# Top.net
KiCad netlist of a schematic drawn in Altium Designer
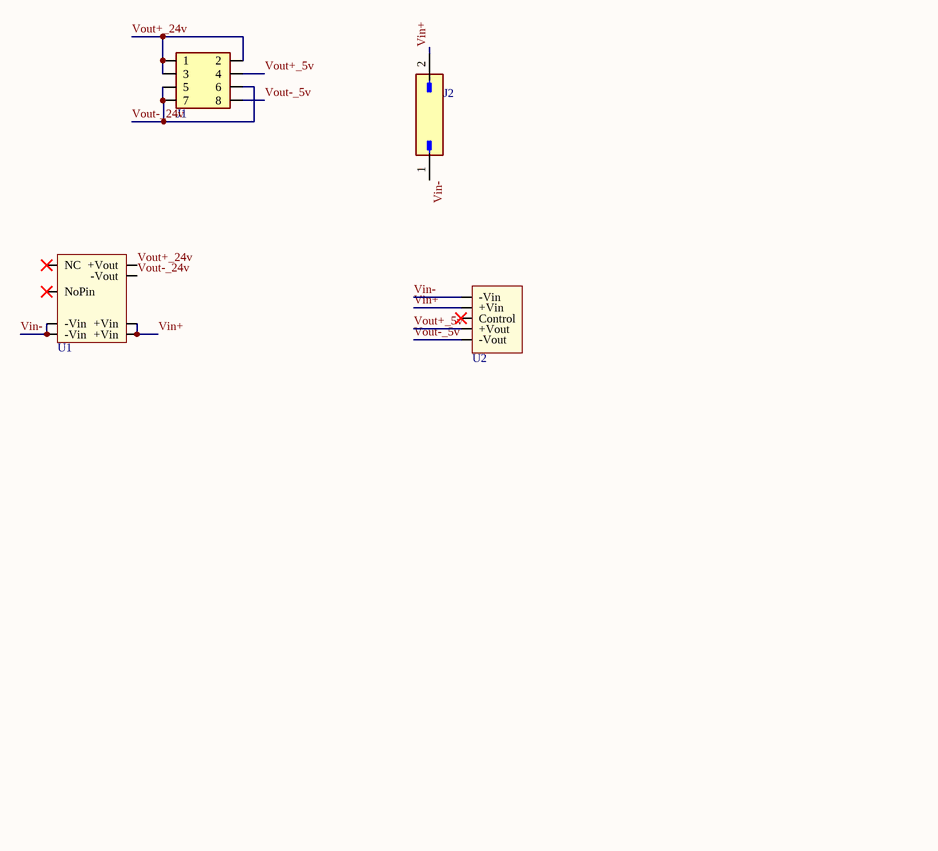
[diagram p0: Top.SchDoc]

(export (version "E")
  (design (tool "Eeschema 10.0.6"))
  (components
    (comp (ref "J1")
      (value "430450800")
      (footprint "MOLEX_430450800")
      (description "Conn 8 Position Throught Hole Dual Row ,Right Angle")
      (fields (field (name "MF") "TE Connectivity") (field (name "MP") "3-794637-8"))
      (libsource (lib "INSU") (part "430450800"))
    )
    (comp (ref "J2")
      (value "436500200")
      (footprint "MOLEX_436500200")
      (description "Connector Molex 2 Pins Right Angle")
      (libsource (lib "INSU") (part "436500200"))
    )
    (comp (ref "U1")
      (value "DJ06S2424A")
      (footprint "DJ06S2424A")
      (description "Convertidores CC/CC aislados (orificio pasante) DC/DC Converter, 24Vout, 6W")
      (libsource (lib "INSU") (part "DJ06S2424A"))
    )
    (comp (ref "U2")
      (value "NCS1S2405SC")
      (footprint "CONV_NCS1S1203SC")
      (description "Convertidores CC/CC aislados (orificio pasante) 1W 24VIN 5VOUT DC/DC")
      (libsource (lib "INSU") (part "NCS1S2405SC"))
    )
  )
  (nets
    (net (code "1") (name "/Vin+") (class "Default")
      (node (ref "J2") (pin "2") (pinfunction "2_2") (pintype "passive"))
      (node (ref "U1") (pin "22") (pinfunction "+Vin_22") (pintype "passive"))
      (node (ref "U1") (pin "23") (pinfunction "+Vin_23") (pintype "passive"))
      (node (ref "U2") (pin "2") (pinfunction "+Vin_2") (pintype "passive"))
    )
    (net (code "2") (name "/Vin-") (class "Default")
      (node (ref "J2") (pin "1") (pinfunction "1_1") (pintype "passive"))
      (node (ref "U1") (pin "2") (pinfunction "-Vin_2") (pintype "passive"))
      (node (ref "U1") (pin "3") (pinfunction "-Vin_3") (pintype "passive"))
      (node (ref "U2") (pin "1") (pinfunction "-Vin_1") (pintype "passive"))
    )
    (net (code "3") (name "/Vout+_5v") (class "Default")
      (node (ref "J1") (pin "4") (pinfunction "4_4") (pintype "passive"))
      (node (ref "U2") (pin "6") (pinfunction "+Vout_6") (pintype "passive"))
    )
    (net (code "4") (name "/Vout+_24v") (class "Default")
      (node (ref "J1") (pin "1") (pinfunction "1_1") (pintype "passive"))
      (node (ref "J1") (pin "2") (pinfunction "2_2") (pintype "passive"))
      (node (ref "J1") (pin "3") (pinfunction "3_3") (pintype "passive"))
      (node (ref "U1") (pin "14") (pinfunction "+Vout_14") (pintype "passive"))
    )
    (net (code "5") (name "/Vout-_5v") (class "Default")
      (node (ref "J1") (pin "8") (pinfunction "8_8") (pintype "passive"))
      (node (ref "U2") (pin "7") (pinfunction "-Vout_7") (pintype "passive"))
    )
    (net (code "6") (name "/Vout-_24v") (class "Default")
      (node (ref "J1") (pin "5") (pinfunction "5_5") (pintype "passive"))
      (node (ref "J1") (pin "6") (pinfunction "6_6") (pintype "passive"))
      (node (ref "J1") (pin "7") (pinfunction "7_7") (pintype "passive"))
      (node (ref "U1") (pin "16") (pinfunction "-Vout_16") (pintype "passive"))
    )
    (net (code "7") (name "unconnected-(U1-NC-Pad11)") (class "Default")
      (node (ref "U1") (pin "11") (pinfunction "NC_11") (pintype "passive+no_connect"))
    )
    (net (code "8") (name "unconnected-(U1-NoPin-Pad9)") (class "Default")
      (node (ref "U1") (pin "9") (pinfunction "NoPin_9") (pintype "passive+no_connect"))
    )
    (net (code "9") (name "unconnected-(U2-Control-Pad3)") (class "Default")
      (node (ref "U2") (pin "3") (pinfunction "Control_3") (pintype "passive+no_connect"))
    )
  )
)
